# Sch_led.net
KiCad netlist of a schematic drawn in Altium Designer
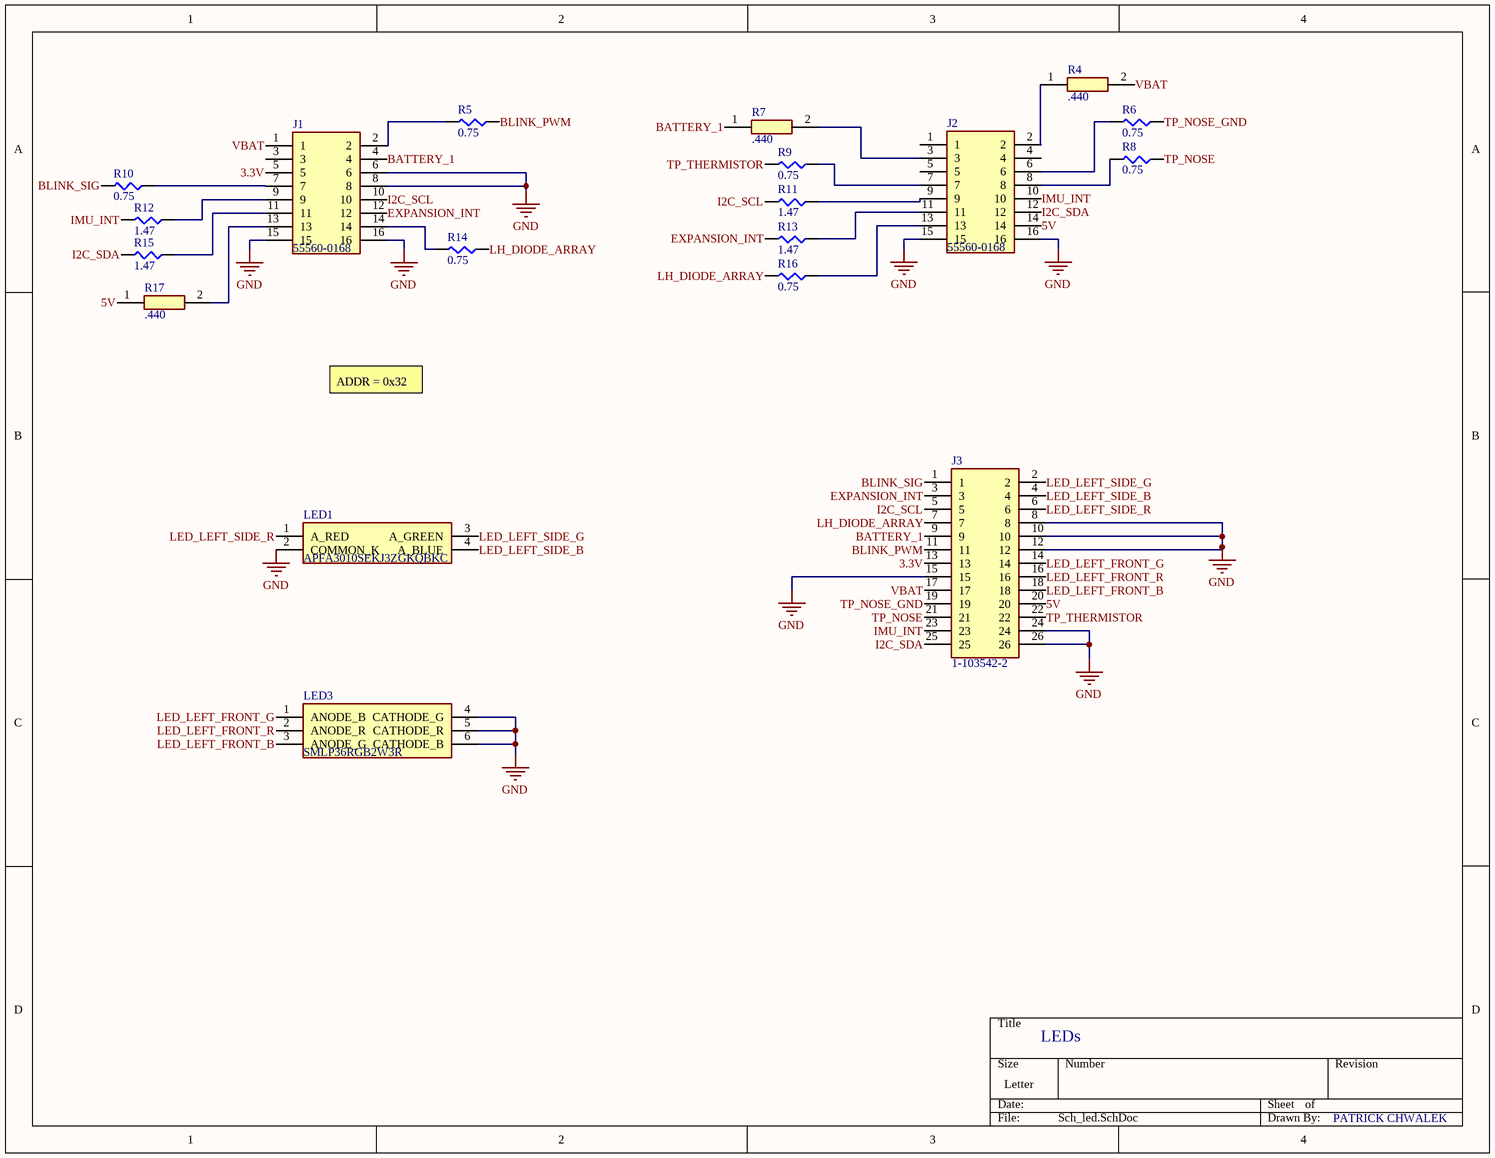
[diagram p0: Sch_led.SchDoc]

(export (version "E")
  (design (tool "Eeschema 10.0.6"))
  (components
    (comp (ref "J1")
      (value "55560-0168")
      (footprint "SamacSys:555600168")
      (description "Connector")
      (fields (field (name "MOUSER PART NUMBER") "538-55560-0168") (field (name "RS PART NUMBER") "7206558P"))
      (libsource (lib "*") (part "55560-0168"))
    )
    (comp (ref "J2")
      (value "55560-0168")
      (footprint "SamacSys:555600168")
      (description "Connector")
      (fields (field (name "MOUSER PART NUMBER") "538-55560-0168") (field (name "RS PART NUMBER") "7206558P"))
      (libsource (lib "*") (part "55560-0168"))
    )
    (comp (ref "J3")
      (value "1-103542-2")
      (footprint "SamacSys:HDRV26W89P254X254_2X13_3261X506X1074P")
      (description "Connector")
      (fields (field (name "MOUSER PART NUMBER") "571-1-103542-2"))
      (libsource (lib "*") (part "1-103542-2"))
    )
    (comp (ref "LED1")
      (value "APFA3010SEKJ3ZGKQBKC")
      (footprint "SamacSys:KPFA-3010RGBC-11")
      (description "LED")
      (fields (field (name "MOUSER PART NUMBER") "604-APFA3010SEKJ3ZGK"))
      (libsource (lib "*") (part "APFA3010SEKJ3ZGKQBKC"))
    )
    (comp (ref "LED3")
      (value "SMLP36RGB2W3R")
      (footprint "ROHM-1510-(0604)")
      (description "LED")
      (fields
        (field (name "MOUSER PART NUMBER") "755-SMLP36RGB2W3R")
        (field (name "RS PART NUMBER") "1246884")
      )
      (libsource (lib "*") (part "SMLP36RGB2W3R"))
    )
    (comp (ref "R4")
      (value ".440")
      (footprint "SamacSys:RESAD1650W60L650D250")
      (description "Resistor (MOX1CT52RR43J)")
      (fields
        (field (name "MANUFACTURER_PART_NUMBER") "MRS25000C1000FCT00")
        (field (name "MOUSER PART NUMBER") "594-MRS25000C1000FCT")
      )
      (libsource (lib "*") (part "MRS25000C1000FCT00"))
    )
    (comp (ref "R5")
      (value "0.75")
      (footprint "SMD-0805-RES")
      (description "RES SMD 0.75 OHM 0805")
      (fields (field (name "PART NUMBER") "ERJ-2GEJ103X") (field (name "DIGI-KEY PART NUMBER") "P10KJCT-ND"))
      (libsource (lib "Panasonic_ERJ_0402") (part "ERJ-2GEJ103X"))
    )
    (comp (ref "R6")
      (value "0.75")
      (footprint "SMD-0805-RES")
      (description "RES SMD 0.75 OHM 0805")
      (fields (field (name "PART NUMBER") "ERJ-2GEJ103X") (field (name "DIGI-KEY PART NUMBER") "P10KJCT-ND"))
      (libsource (lib "Panasonic_ERJ_0402") (part "ERJ-2GEJ103X"))
    )
    (comp (ref "R7")
      (value ".440")
      (footprint "SamacSys:RESAD1650W60L650D250")
      (description "Resistor (MOX1CT52RR43J)")
      (fields
        (field (name "MANUFACTURER_PART_NUMBER") "MRS25000C1000FCT00")
        (field (name "MOUSER PART NUMBER") "594-MRS25000C1000FCT")
      )
      (libsource (lib "*") (part "MRS25000C1000FCT00"))
    )
    (comp (ref "R8")
      (value "0.75")
      (footprint "SMD-0805-RES")
      (description "RES SMD 0.75 OHM 0805")
      (fields (field (name "PART NUMBER") "ERJ-2GEJ103X") (field (name "DIGI-KEY PART NUMBER") "P10KJCT-ND"))
      (libsource (lib "Panasonic_ERJ_0402") (part "ERJ-2GEJ103X"))
    )
    (comp (ref "R9")
      (value "0.75")
      (footprint "SMD-0805-RES")
      (description "RES SMD 0.75 OHM 0805")
      (fields (field (name "PART NUMBER") "ERJ-2GEJ103X") (field (name "DIGI-KEY PART NUMBER") "P10KJCT-ND"))
      (libsource (lib "Panasonic_ERJ_0402") (part "ERJ-2GEJ103X"))
    )
    (comp (ref "R10")
      (value "0.75")
      (footprint "SMD-0805-RES")
      (description "RES SMD 0.75 OHM 0805")
      (fields (field (name "PART NUMBER") "ERJ-2GEJ103X") (field (name "DIGI-KEY PART NUMBER") "P10KJCT-ND"))
      (libsource (lib "Panasonic_ERJ_0402") (part "ERJ-2GEJ103X"))
    )
    (comp (ref "R11")
      (value "1.47")
      (footprint "SMD-0805-RES")
      (description "RES SMD 1.47 OHM 0805")
      (fields (field (name "PART NUMBER") "ERJ-2GEJ103X") (field (name "DIGI-KEY PART NUMBER") "P10KJCT-ND"))
      (libsource (lib "Panasonic_ERJ_0402") (part "ERJ-2GEJ103X"))
    )
    (comp (ref "R12")
      (value "1.47")
      (footprint "SMD-0805-RES")
      (description "RES SMD 1.47 OHM 0805")
      (fields (field (name "PART NUMBER") "ERJ-2GEJ103X") (field (name "DIGI-KEY PART NUMBER") "P10KJCT-ND"))
      (libsource (lib "Panasonic_ERJ_0402") (part "ERJ-2GEJ103X"))
    )
    (comp (ref "R13")
      (value "1.47")
      (footprint "SMD-0805-RES")
      (description "RES SMD 1.47 OHM 0805")
      (fields (field (name "PART NUMBER") "ERJ-2GEJ103X") (field (name "DIGI-KEY PART NUMBER") "P10KJCT-ND"))
      (libsource (lib "Panasonic_ERJ_0402") (part "ERJ-2GEJ103X"))
    )
    (comp (ref "R14")
      (value "0.75")
      (footprint "SMD-0805-RES")
      (description "RES SMD 0.75 OHM 0805")
      (fields (field (name "PART NUMBER") "ERJ-2GEJ103X") (field (name "DIGI-KEY PART NUMBER") "P10KJCT-ND"))
      (libsource (lib "Panasonic_ERJ_0402") (part "ERJ-2GEJ103X"))
    )
    (comp (ref "R15")
      (value "1.47")
      (footprint "SMD-0805-RES")
      (description "RES SMD 1.47 OHM 0805")
      (fields (field (name "PART NUMBER") "ERJ-2GEJ103X") (field (name "DIGI-KEY PART NUMBER") "P10KJCT-ND"))
      (libsource (lib "Panasonic_ERJ_0402") (part "ERJ-2GEJ103X"))
    )
    (comp (ref "R16")
      (value "0.75")
      (footprint "SMD-0805-RES")
      (description "RES SMD 0.75 OHM 0805")
      (fields (field (name "PART NUMBER") "ERJ-2GEJ103X") (field (name "DIGI-KEY PART NUMBER") "P10KJCT-ND"))
      (libsource (lib "Panasonic_ERJ_0402") (part "ERJ-2GEJ103X"))
    )
    (comp (ref "R17")
      (value ".440")
      (footprint "SamacSys:RESAD1650W60L650D250")
      (description "Resistor (MOX1CT52RR43J)")
      (fields
        (field (name "MANUFACTURER_PART_NUMBER") "MRS25000C1000FCT00")
        (field (name "MOUSER PART NUMBER") "594-MRS25000C1000FCT")
      )
      (libsource (lib "*") (part "MRS25000C1000FCT00"))
    )
  )
  (nets
    (net (code "1") (name "/3.3V") (class "Default")
      (node (ref "J1") (pin "5") (pinfunction "5_5") (pintype "passive"))
      (node (ref "J3") (pin "13") (pinfunction "13_13") (pintype "passive"))
    )
    (net (code "2") (name "/5V") (class "Default")
      (node (ref "J2") (pin "14") (pinfunction "14_14") (pintype "passive"))
      (node (ref "J3") (pin "20") (pinfunction "20_20") (pintype "passive"))
      (node (ref "R17") (pin "1") (pinfunction "1_1") (pintype "passive"))
    )
    (net (code "3") (name "/BATTERY_1") (class "Default")
      (node (ref "J1") (pin "4") (pinfunction "4_4") (pintype "passive"))
      (node (ref "J3") (pin "9") (pinfunction "9_9") (pintype "passive"))
      (node (ref "R7") (pin "1") (pinfunction "1_1") (pintype "passive"))
    )
    (net (code "4") (name "/BLINK_PWM") (class "Default")
      (node (ref "J3") (pin "11") (pinfunction "11_11") (pintype "passive"))
      (node (ref "R5") (pin "1") (pinfunction "1_1") (pintype "passive"))
    )
    (net (code "5") (name "/BLINK_SIG") (class "Default")
      (node (ref "J3") (pin "1") (pinfunction "1_1") (pintype "passive"))
      (node (ref "R10") (pin "2") (pinfunction "2_2") (pintype "passive"))
    )
    (net (code "6") (name "/EXPANSION_INT") (class "Default")
      (node (ref "J1") (pin "12") (pinfunction "12_12") (pintype "passive"))
      (node (ref "J3") (pin "3") (pinfunction "3_3") (pintype "passive"))
      (node (ref "R13") (pin "2") (pinfunction "2_2") (pintype "passive"))
    )
    (net (code "7") (name "/I2C_SCL") (class "Default")
      (node (ref "J1") (pin "10") (pinfunction "10_10") (pintype "passive"))
      (node (ref "J3") (pin "5") (pinfunction "5_5") (pintype "passive"))
      (node (ref "R11") (pin "2") (pinfunction "2_2") (pintype "passive"))
    )
    (net (code "8") (name "/I2C_SDA") (class "Default")
      (node (ref "J2") (pin "12") (pinfunction "12_12") (pintype "passive"))
      (node (ref "J3") (pin "25") (pinfunction "25_25") (pintype "passive"))
      (node (ref "R15") (pin "2") (pinfunction "2_2") (pintype "passive"))
    )
    (net (code "9") (name "/IMU_INT") (class "Default")
      (node (ref "J2") (pin "10") (pinfunction "10_10") (pintype "passive"))
      (node (ref "J3") (pin "23") (pinfunction "23_23") (pintype "passive"))
      (node (ref "R12") (pin "2") (pinfunction "2_2") (pintype "passive"))
    )
    (net (code "10") (name "/LED_LEFT_FRONT_B") (class "Default")
      (node (ref "J3") (pin "18") (pinfunction "18_18") (pintype "passive"))
      (node (ref "LED3") (pin "3") (pinfunction "ANODE_G_3") (pintype "passive"))
    )
    (net (code "11") (name "/LED_LEFT_FRONT_G") (class "Default")
      (node (ref "J3") (pin "14") (pinfunction "14_14") (pintype "passive"))
      (node (ref "LED3") (pin "1") (pinfunction "ANODE_B_1") (pintype "passive"))
    )
    (net (code "12") (name "/LED_LEFT_FRONT_R") (class "Default")
      (node (ref "J3") (pin "16") (pinfunction "16_16") (pintype "passive"))
      (node (ref "LED3") (pin "2") (pinfunction "ANODE_R_2") (pintype "passive"))
    )
    (net (code "13") (name "/LED_LEFT_SIDE_B") (class "Default")
      (node (ref "J3") (pin "4") (pinfunction "4_4") (pintype "passive"))
      (node (ref "LED1") (pin "4") (pinfunction "A_BLUE_4") (pintype "passive"))
    )
    (net (code "14") (name "/LED_LEFT_SIDE_G") (class "Default")
      (node (ref "J3") (pin "2") (pinfunction "2_2") (pintype "passive"))
      (node (ref "LED1") (pin "3") (pinfunction "A_GREEN_3") (pintype "passive"))
    )
    (net (code "15") (name "/LED_LEFT_SIDE_R") (class "Default")
      (node (ref "J3") (pin "6") (pinfunction "6_6") (pintype "passive"))
      (node (ref "LED1") (pin "1") (pinfunction "A_RED_1") (pintype "passive"))
    )
    (net (code "16") (name "/LH_DIODE_ARRAY") (class "Default")
      (node (ref "J3") (pin "7") (pinfunction "7_7") (pintype "passive"))
      (node (ref "R14") (pin "1") (pinfunction "1_1") (pintype "passive"))
      (node (ref "R16") (pin "2") (pinfunction "2_2") (pintype "passive"))
    )
    (net (code "17") (name "/TP_NOSE") (class "Default")
      (node (ref "J3") (pin "21") (pinfunction "21_21") (pintype "passive"))
      (node (ref "R8") (pin "1") (pinfunction "1_1") (pintype "passive"))
    )
    (net (code "18") (name "/TP_NOSE_GND") (class "Default")
      (node (ref "J3") (pin "19") (pinfunction "19_19") (pintype "passive"))
      (node (ref "R6") (pin "1") (pinfunction "1_1") (pintype "passive"))
    )
    (net (code "19") (name "/TP_THERMISTOR") (class "Default")
      (node (ref "J3") (pin "22") (pinfunction "22_22") (pintype "passive"))
      (node (ref "R9") (pin "2") (pinfunction "2_2") (pintype "passive"))
    )
    (net (code "20") (name "/VBAT") (class "Default")
      (node (ref "J1") (pin "1") (pinfunction "1_1") (pintype "passive"))
      (node (ref "J3") (pin "17") (pinfunction "17_17") (pintype "passive"))
      (node (ref "R4") (pin "2") (pinfunction "2_2") (pintype "passive"))
    )
    (net (code "21") (name "GND") (class "Default")
      (node (ref "J1") (pin "15") (pinfunction "15_15") (pintype "passive"))
      (node (ref "J1") (pin "16") (pinfunction "16_16") (pintype "passive"))
      (node (ref "J1") (pin "6") (pinfunction "6_6") (pintype "passive"))
      (node (ref "J1") (pin "8") (pinfunction "8_8") (pintype "passive"))
      (node (ref "J2") (pin "15") (pinfunction "15_15") (pintype "passive"))
      (node (ref "J2") (pin "16") (pinfunction "16_16") (pintype "passive"))
      (node (ref "J3") (pin "10") (pinfunction "10_10") (pintype "passive"))
      (node (ref "J3") (pin "12") (pinfunction "12_12") (pintype "passive"))
      (node (ref "J3") (pin "15") (pinfunction "15_15") (pintype "passive"))
      (node (ref "J3") (pin "24") (pinfunction "24_24") (pintype "passive"))
      (node (ref "J3") (pin "26") (pinfunction "26_26") (pintype "passive"))
      (node (ref "J3") (pin "8") (pinfunction "8_8") (pintype "passive"))
      (node (ref "LED1") (pin "2") (pinfunction "COMMON_K_2") (pintype "passive"))
      (node (ref "LED3") (pin "4") (pinfunction "CATHODE_G_4") (pintype "passive"))
      (node (ref "LED3") (pin "5") (pinfunction "CATHODE_R_5") (pintype "passive"))
      (node (ref "LED3") (pin "6") (pinfunction "CATHODE_B_6") (pintype "passive"))
    )
    (net (code "22") (name "Net-(J1-Pad2)") (class "Default")
      (node (ref "J1") (pin "2") (pinfunction "2_2") (pintype "passive"))
      (node (ref "R5") (pin "2") (pinfunction "2_2") (pintype "passive"))
    )
    (net (code "23") (name "Net-(J1-Pad7)") (class "Default")
      (node (ref "J1") (pin "7") (pinfunction "7_7") (pintype "passive"))
      (node (ref "R10") (pin "1") (pinfunction "1_1") (pintype "passive"))
    )
    (net (code "24") (name "Net-(J1-Pad9)") (class "Default")
      (node (ref "J1") (pin "9") (pinfunction "9_9") (pintype "passive"))
      (node (ref "R12") (pin "1") (pinfunction "1_1") (pintype "passive"))
    )
    (net (code "25") (name "Net-(J1-Pad11)") (class "Default")
      (node (ref "J1") (pin "11") (pinfunction "11_11") (pintype "passive"))
      (node (ref "R15") (pin "1") (pinfunction "1_1") (pintype "passive"))
    )
    (net (code "26") (name "Net-(J1-Pad13)") (class "Default")
      (node (ref "J1") (pin "13") (pinfunction "13_13") (pintype "passive"))
      (node (ref "R17") (pin "2") (pinfunction "2_2") (pintype "passive"))
    )
    (net (code "27") (name "Net-(J1-Pad14)") (class "Default")
      (node (ref "J1") (pin "14") (pinfunction "14_14") (pintype "passive"))
      (node (ref "R14") (pin "2") (pinfunction "2_2") (pintype "passive"))
    )
    (net (code "28") (name "Net-(J2-Pad2)") (class "Default")
      (node (ref "J2") (pin "2") (pinfunction "2_2") (pintype "passive"))
      (node (ref "R4") (pin "1") (pinfunction "1_1") (pintype "passive"))
    )
    (net (code "29") (name "Net-(J2-Pad3)") (class "Default")
      (node (ref "J2") (pin "3") (pinfunction "3_3") (pintype "passive"))
      (node (ref "R7") (pin "2") (pinfunction "2_2") (pintype "passive"))
    )
    (net (code "30") (name "Net-(J2-Pad6)") (class "Default")
      (node (ref "J2") (pin "6") (pinfunction "6_6") (pintype "passive"))
      (node (ref "R6") (pin "2") (pinfunction "2_2") (pintype "passive"))
    )
    (net (code "31") (name "Net-(J2-Pad7)") (class "Default")
      (node (ref "J2") (pin "7") (pinfunction "7_7") (pintype "passive"))
      (node (ref "R9") (pin "1") (pinfunction "1_1") (pintype "passive"))
    )
    (net (code "32") (name "Net-(J2-Pad8)") (class "Default")
      (node (ref "J2") (pin "8") (pinfunction "8_8") (pintype "passive"))
      (node (ref "R8") (pin "2") (pinfunction "2_2") (pintype "passive"))
    )
    (net (code "33") (name "Net-(J2-Pad9)") (class "Default")
      (node (ref "J2") (pin "9") (pinfunction "9_9") (pintype "passive"))
      (node (ref "R11") (pin "1") (pinfunction "1_1") (pintype "passive"))
    )
    (net (code "34") (name "Net-(J2-Pad11)") (class "Default")
      (node (ref "J2") (pin "11") (pinfunction "11_11") (pintype "passive"))
      (node (ref "R13") (pin "1") (pinfunction "1_1") (pintype "passive"))
    )
    (net (code "35") (name "Net-(J2-Pad13)") (class "Default")
      (node (ref "J2") (pin "13") (pinfunction "13_13") (pintype "passive"))
      (node (ref "R16") (pin "1") (pinfunction "1_1") (pintype "passive"))
    )
    (net (code "36") (name "unconnected-(J1-Pad3)") (class "Default")
      (node (ref "J1") (pin "3") (pinfunction "3_3") (pintype "passive"))
    )
    (net (code "37") (name "unconnected-(J2-Pad1)") (class "Default")
      (node (ref "J2") (pin "1") (pinfunction "1_1") (pintype "passive"))
    )
    (net (code "38") (name "unconnected-(J2-Pad4)") (class "Default")
      (node (ref "J2") (pin "4") (pinfunction "4_4") (pintype "passive"))
    )
    (net (code "39") (name "unconnected-(J2-Pad5)") (class "Default")
      (node (ref "J2") (pin "5") (pinfunction "5_5") (pintype "passive"))
    )
  )
)
